# Vorlage_ATmega2560-16AU.net
KiCad netlist of a schematic drawn in EAGLE
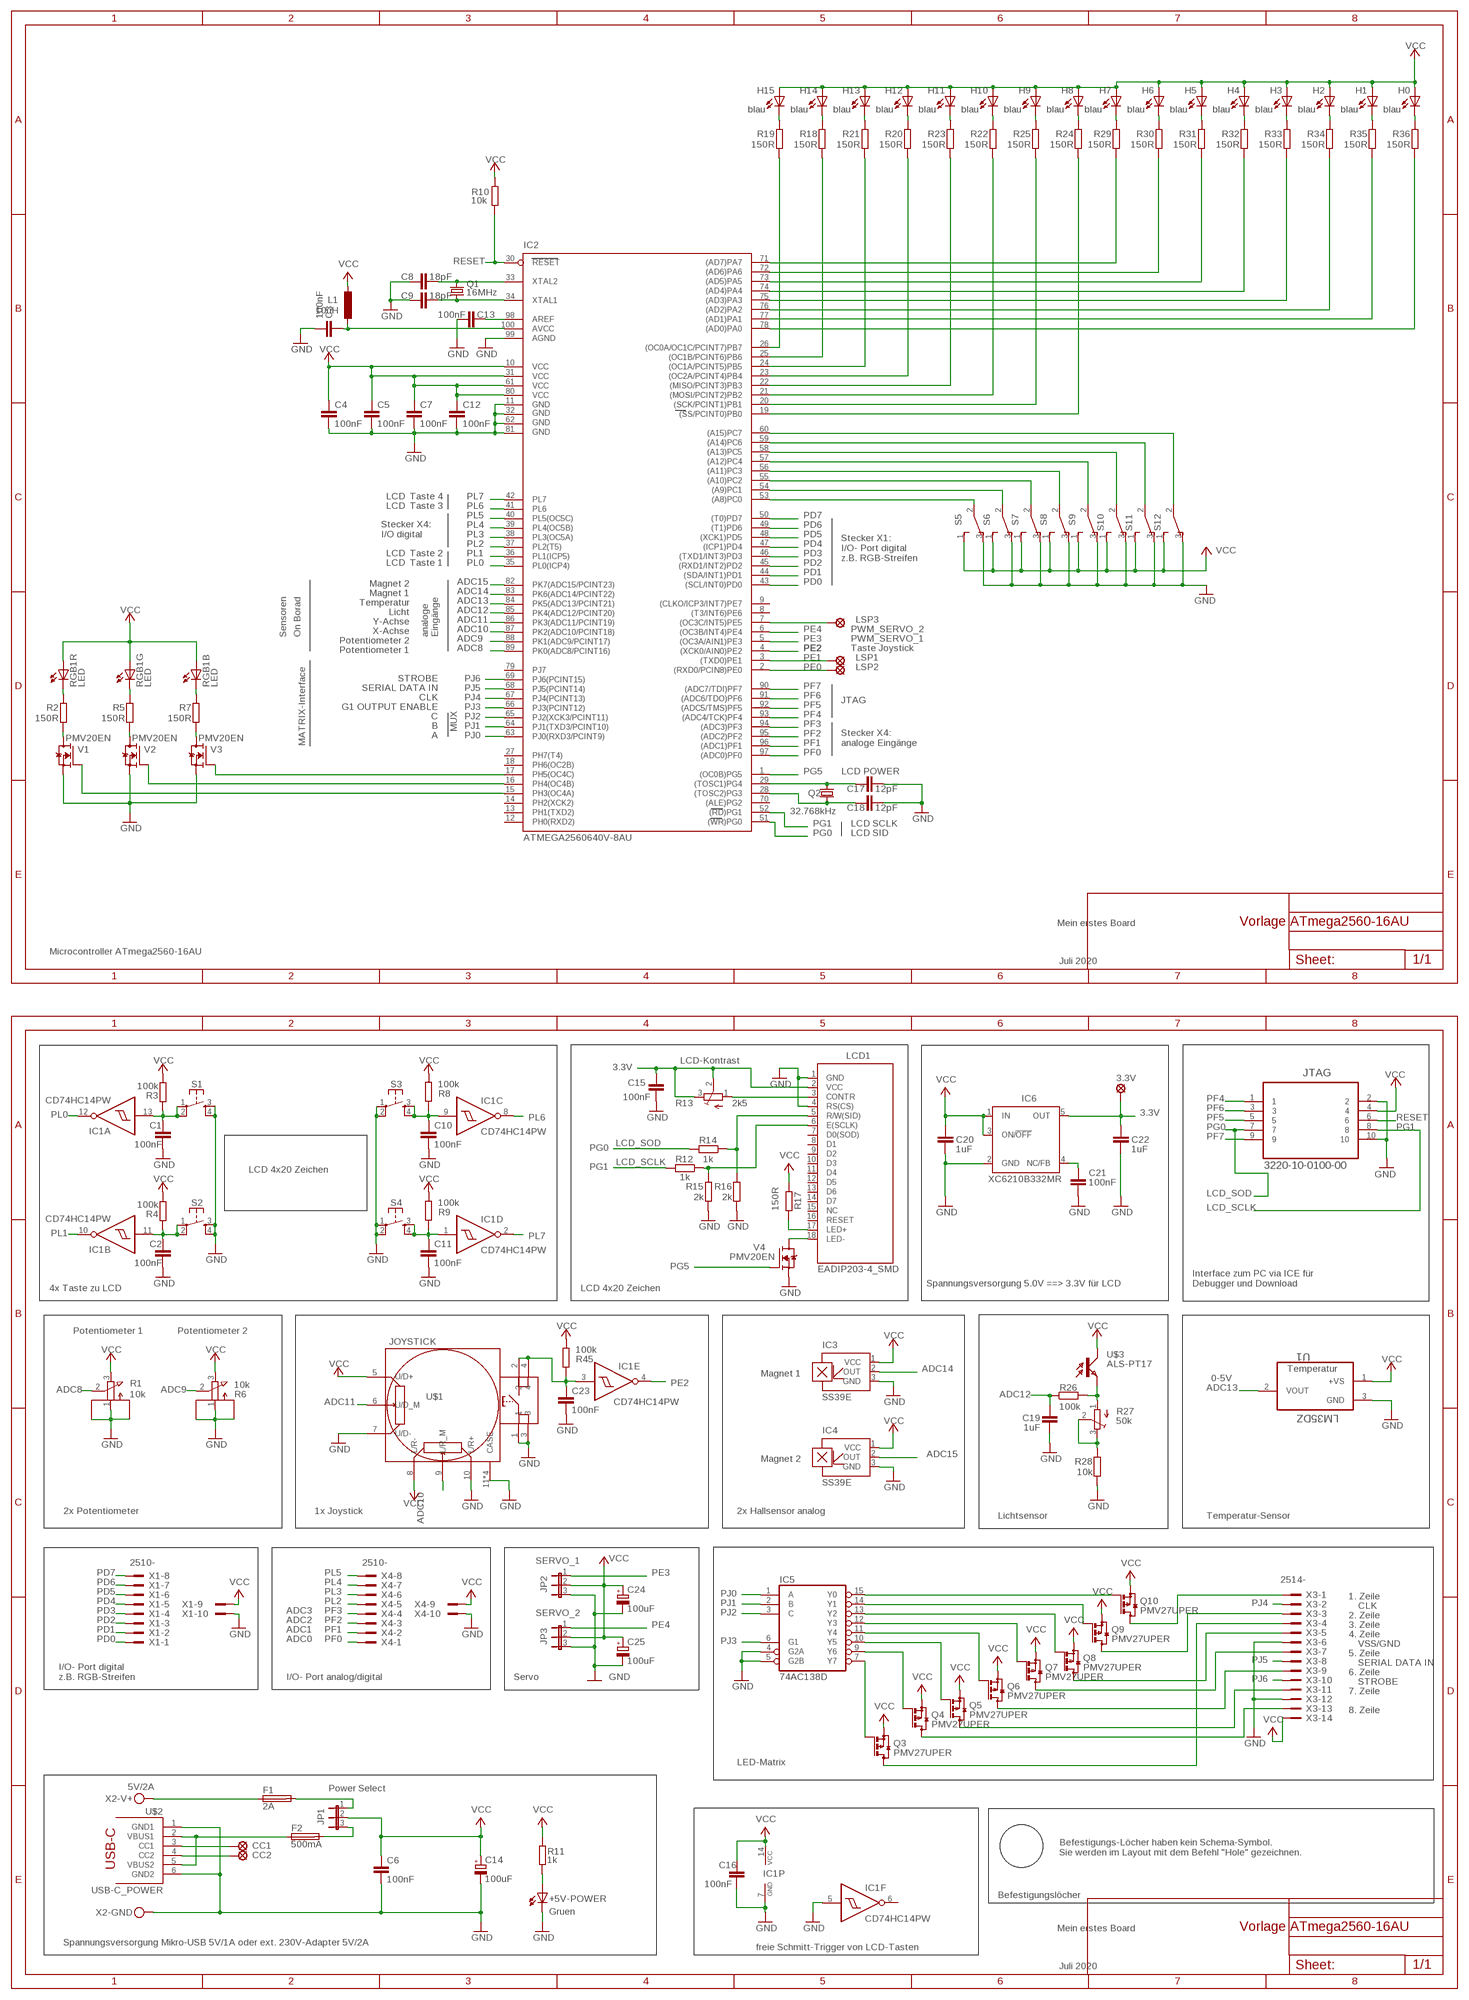
[diagram p0: schematic, sheet 1]

(export (version "E")
  (design (tool "Eeschema 10.0.6"))
  (components
    (comp (ref "+5V-POWER")
      (value "Gruen")
      (footprint "eagle-import:CHIPLED_1206")
      (libsource (lib "eagle-import") (part "LEDCHIPLED_1206"))
    )
    (comp (ref "3.3V")
      (value "3.3V")
      (footprint "eagle-import:LSP11")
      (libsource (lib "eagle-import") (part "LSP11"))
    )
    (comp (ref "C1")
      (value "100nF")
      (footprint "eagle-import:C1206")
      (libsource (lib "eagle-import") (part "C-EUC1206"))
    )
    (comp (ref "C2")
      (value "100nF")
      (footprint "eagle-import:C1206")
      (libsource (lib "eagle-import") (part "C-EUC1206"))
    )
    (comp (ref "C3")
      (value "100nF")
      (footprint "eagle-import:C1206")
      (libsource (lib "eagle-import") (part "C-EUC1206"))
    )
    (comp (ref "C4")
      (value "100nF")
      (footprint "eagle-import:C1206")
      (libsource (lib "eagle-import") (part "C-EUC1206"))
    )
    (comp (ref "C5")
      (value "100nF")
      (footprint "eagle-import:C1206")
      (libsource (lib "eagle-import") (part "C-EUC1206"))
    )
    (comp (ref "C6")
      (value "100nF")
      (footprint "eagle-import:C1206")
      (libsource (lib "eagle-import") (part "C-EUC1206"))
    )
    (comp (ref "C7")
      (value "100nF")
      (footprint "eagle-import:C1206")
      (libsource (lib "eagle-import") (part "C-EUC1206"))
    )
    (comp (ref "C8")
      (value "18pF")
      (footprint "eagle-import:C0805K")
      (libsource (lib "eagle-import") (part "C-EUC0805K"))
    )
    (comp (ref "C9")
      (value "18pF")
      (footprint "eagle-import:C0805K")
      (libsource (lib "eagle-import") (part "C-EUC0805K"))
    )
    (comp (ref "C10")
      (value "100nF")
      (footprint "eagle-import:C1206")
      (libsource (lib "eagle-import") (part "C-EUC1206"))
    )
    (comp (ref "C11")
      (value "100nF")
      (footprint "eagle-import:C1206")
      (libsource (lib "eagle-import") (part "C-EUC1206"))
    )
    (comp (ref "C12")
      (value "100nF")
      (footprint "eagle-import:C1206")
      (libsource (lib "eagle-import") (part "C-EUC1206"))
    )
    (comp (ref "C13")
      (value "100nF")
      (footprint "eagle-import:C1206")
      (libsource (lib "eagle-import") (part "C-EUC1206"))
    )
    (comp (ref "C14")
      (value "100uF")
      (footprint "eagle-import:UD-6,3X5,8_NICHICON")
      (libsource (lib "eagle-import") (part "CPOL-EUUD-6,3X8,8"))
    )
    (comp (ref "C15")
      (value "100nF")
      (footprint "eagle-import:C1206")
      (libsource (lib "eagle-import") (part "C-EUC1206"))
    )
    (comp (ref "C16")
      (value "100nF")
      (footprint "eagle-import:C1206")
      (libsource (lib "eagle-import") (part "C-EUC1206"))
    )
    (comp (ref "C17")
      (value "12pF")
      (footprint "eagle-import:C0805K")
      (libsource (lib "eagle-import") (part "C-EUC0805K"))
    )
    (comp (ref "C18")
      (value "12pF")
      (footprint "eagle-import:C0805K")
      (libsource (lib "eagle-import") (part "C-EUC0805K"))
    )
    (comp (ref "C19")
      (value "1uF")
      (footprint "eagle-import:C1206")
      (libsource (lib "eagle-import") (part "C-EUC1206"))
    )
    (comp (ref "C20")
      (value "1uF")
      (footprint "eagle-import:C1206")
      (libsource (lib "eagle-import") (part "C-EUC1206"))
    )
    (comp (ref "C21")
      (value "100nF")
      (footprint "eagle-import:C1206")
      (libsource (lib "eagle-import") (part "C-EUC1206"))
    )
    (comp (ref "C22")
      (value "1uF")
      (footprint "eagle-import:C1206")
      (libsource (lib "eagle-import") (part "C-EUC1206"))
    )
    (comp (ref "C23")
      (value "100nF")
      (footprint "eagle-import:C1206")
      (libsource (lib "eagle-import") (part "C-EUC1206"))
    )
    (comp (ref "C24")
      (value "100uF")
      (footprint "eagle-import:UD-6,3X5,8_NICHICON")
      (libsource (lib "eagle-import") (part "CPOL-EUUD-6,3X8,8"))
    )
    (comp (ref "C25")
      (value "100uF")
      (footprint "eagle-import:UD-6,3X5,8_NICHICON")
      (libsource (lib "eagle-import") (part "CPOL-EUUD-6,3X8,8"))
    )
    (comp (ref "CC1")
      (value "LSP11")
      (footprint "eagle-import:LSP11")
      (libsource (lib "eagle-import") (part "LSP11"))
    )
    (comp (ref "CC2")
      (value "LSP11")
      (footprint "eagle-import:LSP11")
      (libsource (lib "eagle-import") (part "LSP11"))
    )
    (comp (ref "F1")
      (value "2A")
      (footprint "eagle-import:F1206")
      (libsource (lib "eagle-import") (part "195601206"))
    )
    (comp (ref "F2")
      (value "500mA")
      (footprint "eagle-import:F1206")
      (libsource (lib "eagle-import") (part "195601206"))
    )
    (comp (ref "H0")
      (value "blau")
      (footprint "eagle-import:CHIPLED_1206")
      (libsource (lib "eagle-import") (part "LEDCHIPLED_1206"))
    )
    (comp (ref "H1")
      (value "blau")
      (footprint "eagle-import:CHIPLED_1206")
      (libsource (lib "eagle-import") (part "LEDCHIPLED_1206"))
    )
    (comp (ref "H2")
      (value "blau")
      (footprint "eagle-import:CHIPLED_1206")
      (libsource (lib "eagle-import") (part "LEDCHIPLED_1206"))
    )
    (comp (ref "H3")
      (value "blau")
      (footprint "eagle-import:CHIPLED_1206")
      (libsource (lib "eagle-import") (part "LEDCHIPLED_1206"))
    )
    (comp (ref "H4")
      (value "blau")
      (footprint "eagle-import:CHIPLED_1206")
      (libsource (lib "eagle-import") (part "LEDCHIPLED_1206"))
    )
    (comp (ref "H5")
      (value "blau")
      (footprint "eagle-import:CHIPLED_1206")
      (libsource (lib "eagle-import") (part "LEDCHIPLED_1206"))
    )
    (comp (ref "H6")
      (value "blau")
      (footprint "eagle-import:CHIPLED_1206")
      (libsource (lib "eagle-import") (part "LEDCHIPLED_1206"))
    )
    (comp (ref "H7")
      (value "blau")
      (footprint "eagle-import:CHIPLED_1206")
      (libsource (lib "eagle-import") (part "LEDCHIPLED_1206"))
    )
    (comp (ref "H8")
      (value "blau")
      (footprint "eagle-import:CHIPLED_1206")
      (libsource (lib "eagle-import") (part "LEDCHIPLED_1206"))
    )
    (comp (ref "H9")
      (value "blau")
      (footprint "eagle-import:CHIPLED_1206")
      (libsource (lib "eagle-import") (part "LEDCHIPLED_1206"))
    )
    (comp (ref "H10")
      (value "blau")
      (footprint "eagle-import:CHIPLED_1206")
      (libsource (lib "eagle-import") (part "LEDCHIPLED_1206"))
    )
    (comp (ref "H11")
      (value "blau")
      (footprint "eagle-import:CHIPLED_1206")
      (libsource (lib "eagle-import") (part "LEDCHIPLED_1206"))
    )
    (comp (ref "H12")
      (value "blau")
      (footprint "eagle-import:CHIPLED_1206")
      (libsource (lib "eagle-import") (part "LEDCHIPLED_1206"))
    )
    (comp (ref "H13")
      (value "blau")
      (footprint "eagle-import:CHIPLED_1206")
      (libsource (lib "eagle-import") (part "LEDCHIPLED_1206"))
    )
    (comp (ref "H14")
      (value "blau")
      (footprint "eagle-import:CHIPLED_1206")
      (libsource (lib "eagle-import") (part "LEDCHIPLED_1206"))
    )
    (comp (ref "H15")
      (value "blau")
      (footprint "eagle-import:CHIPLED_1206")
      (libsource (lib "eagle-import") (part "LEDCHIPLED_1206"))
    )
    (comp (ref "IC1")
      (value "CD74HC14PW")
      (footprint "eagle-import:SO14")
      (libsource (lib "eagle-import") (part "7414D"))
    )
    (comp (ref "IC2")
      (value "ATMEGA2560640V-8AU")
      (footprint "eagle-import:TQFP100")
      (libsource (lib "eagle-import") (part "ATMEGA2560AU640V-8"))
    )
    (comp (ref "IC3")
      (value "SS39E")
      (footprint "eagle-import:SOT23-W")
      (fields (field (name "MF") "ALLEGRO MICROSYSTEMS, INC.") (field (name "MPN") "A1301ELHLT-T"))
      (libsource (lib "eagle-import") (part "A13?LH01"))
    )
    (comp (ref "IC4")
      (value "SS39E")
      (footprint "eagle-import:SOT23-W")
      (fields (field (name "MF") "ALLEGRO MICROSYSTEMS, INC.") (field (name "MPN") "A1301ELHLT-T"))
      (libsource (lib "eagle-import") (part "A13?LH01"))
    )
    (comp (ref "IC5")
      (value "74AC138D")
      (footprint "eagle-import:SO16")
      (libsource (lib "eagle-import") (part "74138DAC"))
    )
    (comp (ref "IC6")
      (value "XC6210B332MR")
      (footprint "eagle-import:SOT23-DBV")
      (libsource (lib "eagle-import") (part "LP2985-XXDBVR"))
    )
    (comp (ref "JP1")
      (value "Power Select")
      (footprint "eagle-import:JP2")
      (libsource (lib "eagle-import") (part "JP2E"))
    )
    (comp (ref "JP2")
      (value "SERVO_1")
      (footprint "eagle-import:JP2")
      (libsource (lib "eagle-import") (part "JP2E"))
    )
    (comp (ref "JP3")
      (value "SERVO_2")
      (footprint "eagle-import:JP2")
      (libsource (lib "eagle-import") (part "JP2E"))
    )
    (comp (ref "JTAG")
      (value "3220-10-0100-00")
      (footprint "eagle-import:SAMTEC_FTS-105-01-L-D")
      (fields (field (name "MPN") "FTS-105-01-L-D"))
      (libsource (lib "eagle-import") (part "FTS-105-01-L-D"))
    )
    (comp (ref "L1")
      (value "10uH")
      (footprint "eagle-import:L2825P")
      (libsource (lib "eagle-import") (part "L-EUL2825P"))
    )
    (comp (ref "LCD1")
      (value "EADIP203-4_SMD")
      (footprint "eagle-import:EADIP203-4SMD")
      (libsource (lib "eagle-import") (part "EADIP203-4EADIP203-4SMD"))
    )
    (comp (ref "LSP1")
      (value "LSP11")
      (footprint "eagle-import:LSP11")
      (libsource (lib "eagle-import") (part "LSP11"))
    )
    (comp (ref "LSP2")
      (value "LSP11")
      (footprint "eagle-import:LSP11")
      (libsource (lib "eagle-import") (part "LSP11"))
    )
    (comp (ref "LSP3")
      (value "LSP11")
      (footprint "eagle-import:LSP11")
      (libsource (lib "eagle-import") (part "LSP11"))
    )
    (comp (ref "Q1")
      (value "16MHz")
      (footprint "eagle-import:HC49UP")
      (libsource (lib "eagle-import") (part "CRYSTALHC49UP"))
    )
    (comp (ref "Q2")
      (value "32.768kHz")
      (footprint "eagle-import:TC38H")
      (libsource (lib "eagle-import") (part "CRYSTALTC38H"))
    )
    (comp (ref "Q3")
      (value "PMV27UPER")
      (footprint "eagle-import:SOT23")
      (libsource (lib "eagle-import") (part "BSS84"))
    )
    (comp (ref "Q4")
      (value "PMV27UPER")
      (footprint "eagle-import:SOT23")
      (libsource (lib "eagle-import") (part "BSS84"))
    )
    (comp (ref "Q5")
      (value "PMV27UPER")
      (footprint "eagle-import:SOT23")
      (libsource (lib "eagle-import") (part "BSS84"))
    )
    (comp (ref "Q6")
      (value "PMV27UPER")
      (footprint "eagle-import:SOT23")
      (libsource (lib "eagle-import") (part "BSS84"))
    )
    (comp (ref "Q7")
      (value "PMV27UPER")
      (footprint "eagle-import:SOT23")
      (libsource (lib "eagle-import") (part "BSS84"))
    )
    (comp (ref "Q8")
      (value "PMV27UPER")
      (footprint "eagle-import:SOT23")
      (libsource (lib "eagle-import") (part "BSS84"))
    )
    (comp (ref "Q9")
      (value "PMV27UPER")
      (footprint "eagle-import:SOT23")
      (libsource (lib "eagle-import") (part "BSS84"))
    )
    (comp (ref "Q10")
      (value "PMV27UPER")
      (footprint "eagle-import:SOT23")
      (libsource (lib "eagle-import") (part "BSS84"))
    )
    (comp (ref "R1")
      (value "10k")
      (footprint "eagle-import:EVUF")
      (libsource (lib "eagle-import") (part "EVUA"))
    )
    (comp (ref "R2")
      (value "150R")
      (footprint "eagle-import:R1206")
      (libsource (lib "eagle-import") (part "R-EU_R1206"))
    )
    (comp (ref "R3")
      (value "100k")
      (footprint "eagle-import:R1206")
      (libsource (lib "eagle-import") (part "R-EU_R1206"))
    )
    (comp (ref "R4")
      (value "100k")
      (footprint "eagle-import:R1206")
      (libsource (lib "eagle-import") (part "R-EU_R1206"))
    )
    (comp (ref "R5")
      (value "150R")
      (footprint "eagle-import:R1206")
      (libsource (lib "eagle-import") (part "R-EU_R1206"))
    )
    (comp (ref "R6")
      (value "10k")
      (footprint "eagle-import:EVUF")
      (libsource (lib "eagle-import") (part "EVUA"))
    )
    (comp (ref "R7")
      (value "150R")
      (footprint "eagle-import:R1206")
      (libsource (lib "eagle-import") (part "R-EU_R1206"))
    )
    (comp (ref "R8")
      (value "100k")
      (footprint "eagle-import:R1206")
      (libsource (lib "eagle-import") (part "R-EU_R1206"))
    )
    (comp (ref "R9")
      (value "100k")
      (footprint "eagle-import:R1206")
      (libsource (lib "eagle-import") (part "R-EU_R1206"))
    )
    (comp (ref "R10")
      (value "10k")
      (footprint "eagle-import:R1206")
      (libsource (lib "eagle-import") (part "R-EU_R1206"))
    )
    (comp (ref "R11")
      (value "1k")
      (footprint "eagle-import:R1206")
      (libsource (lib "eagle-import") (part "R-EU_R1206"))
    )
    (comp (ref "R12")
      (value "1k")
      (footprint "eagle-import:R1206")
      (libsource (lib "eagle-import") (part "R-EU_R1206"))
    )
    (comp (ref "R13")
      (value "2k5")
      (footprint "eagle-import:3223G")
      (libsource (lib "eagle-import") (part "TRIM_EU-3223G"))
    )
    (comp (ref "R14")
      (value "1k")
      (footprint "eagle-import:R1206")
      (libsource (lib "eagle-import") (part "R-EU_R1206"))
    )
    (comp (ref "R15")
      (value "2k")
      (footprint "eagle-import:R1206")
      (libsource (lib "eagle-import") (part "R-EU_R1206"))
    )
    (comp (ref "R16")
      (value "2k")
      (footprint "eagle-import:R1206")
      (libsource (lib "eagle-import") (part "R-EU_R1206"))
    )
    (comp (ref "R17")
      (value "150R")
      (footprint "eagle-import:R1206")
      (libsource (lib "eagle-import") (part "R-EU_R1206"))
    )
    (comp (ref "R18")
      (value "150R")
      (footprint "eagle-import:R1206")
      (libsource (lib "eagle-import") (part "R-EU_R1206"))
    )
    (comp (ref "R19")
      (value "150R")
      (footprint "eagle-import:R1206")
      (libsource (lib "eagle-import") (part "R-EU_R1206"))
    )
    (comp (ref "R20")
      (value "150R")
      (footprint "eagle-import:R1206")
      (libsource (lib "eagle-import") (part "R-EU_R1206"))
    )
    (comp (ref "R21")
      (value "150R")
      (footprint "eagle-import:R1206")
      (libsource (lib "eagle-import") (part "R-EU_R1206"))
    )
    (comp (ref "R22")
      (value "150R")
      (footprint "eagle-import:R1206")
      (libsource (lib "eagle-import") (part "R-EU_R1206"))
    )
    (comp (ref "R23")
      (value "150R")
      (footprint "eagle-import:R1206")
      (libsource (lib "eagle-import") (part "R-EU_R1206"))
    )
    (comp (ref "R24")
      (value "150R")
      (footprint "eagle-import:R1206")
      (libsource (lib "eagle-import") (part "R-EU_R1206"))
    )
    (comp (ref "R25")
      (value "150R")
      (footprint "eagle-import:R1206")
      (libsource (lib "eagle-import") (part "R-EU_R1206"))
    )
    (comp (ref "R26")
      (value "100k")
      (footprint "eagle-import:R1206")
      (libsource (lib "eagle-import") (part "R-EU_R1206"))
    )
    (comp (ref "R27")
      (value "50k")
      (footprint "eagle-import:3223G")
      (libsource (lib "eagle-import") (part "TRIM_EU-3223G"))
    )
    (comp (ref "R28")
      (value "10k")
      (footprint "eagle-import:R1206")
      (libsource (lib "eagle-import") (part "R-EU_R1206"))
    )
    (comp (ref "R29")
      (value "150R")
      (footprint "eagle-import:R1206")
      (libsource (lib "eagle-import") (part "R-EU_R1206"))
    )
    (comp (ref "R30")
      (value "150R")
      (footprint "eagle-import:R1206")
      (libsource (lib "eagle-import") (part "R-EU_R1206"))
    )
    (comp (ref "R31")
      (value "150R")
      (footprint "eagle-import:R1206")
      (libsource (lib "eagle-import") (part "R-EU_R1206"))
    )
    (comp (ref "R32")
      (value "150R")
      (footprint "eagle-import:R1206")
      (libsource (lib "eagle-import") (part "R-EU_R1206"))
    )
    (comp (ref "R33")
      (value "150R")
      (footprint "eagle-import:R1206")
      (libsource (lib "eagle-import") (part "R-EU_R1206"))
    )
    (comp (ref "R34")
      (value "150R")
      (footprint "eagle-import:R1206")
      (libsource (lib "eagle-import") (part "R-EU_R1206"))
    )
    (comp (ref "R35")
      (value "150R")
      (footprint "eagle-import:R1206")
      (libsource (lib "eagle-import") (part "R-EU_R1206"))
    )
    (comp (ref "R36")
      (value "150R")
      (footprint "eagle-import:R1206")
      (libsource (lib "eagle-import") (part "R-EU_R1206"))
    )
    (comp (ref "R45")
      (value "100k")
      (footprint "eagle-import:R1206")
      (libsource (lib "eagle-import") (part "R-EU_R1206"))
    )
    (comp (ref "RGB1")
      (value "LED")
      (footprint "eagle-import:LED_MIT_DIFUSOR")
      (libsource (lib "eagle-import") (part "GM5WA94310AMIT_DIFUSOR"))
    )
    (comp (ref "S1")
      (value "TS42_4PAD")
      (footprint "eagle-import:TS42_4PAD")
      (libsource (lib "eagle-import") (part "TS42_4PAD"))
    )
    (comp (ref "S2")
      (value "TS42_4PAD")
      (footprint "eagle-import:TS42_4PAD")
      (libsource (lib "eagle-import") (part "TS42_4PAD"))
    )
    (comp (ref "S3")
      (value "TS42_4PAD")
      (footprint "eagle-import:TS42_4PAD")
      (libsource (lib "eagle-import") (part "TS42_4PAD"))
    )
    (comp (ref "S4")
      (value "TS42_4PAD")
      (footprint "eagle-import:TS42_4PAD")
      (libsource (lib "eagle-import") (part "TS42_4PAD"))
    )
    (comp (ref "S5")
      (value "TL36POSPDT_5MM")
      (footprint "eagle-import:SPDT_5MM")
      (libsource (lib "eagle-import") (part "TL36POSPDT_5MM"))
    )
    (comp (ref "S6")
      (value "TL36POSPDT_5MM")
      (footprint "eagle-import:SPDT_5MM")
      (libsource (lib "eagle-import") (part "TL36POSPDT_5MM"))
    )
    (comp (ref "S7")
      (value "TL36POSPDT_5MM")
      (footprint "eagle-import:SPDT_5MM")
      (libsource (lib "eagle-import") (part "TL36POSPDT_5MM"))
    )
    (comp (ref "S8")
      (value "TL36POSPDT_5MM")
      (footprint "eagle-import:SPDT_5MM")
      (libsource (lib "eagle-import") (part "TL36POSPDT_5MM"))
    )
    (comp (ref "S9")
      (value "TL36POSPDT_5MM")
      (footprint "eagle-import:SPDT_5MM")
      (libsource (lib "eagle-import") (part "TL36POSPDT_5MM"))
    )
    (comp (ref "S10")
      (value "TL36POSPDT_5MM")
      (footprint "eagle-import:SPDT_5MM")
      (libsource (lib "eagle-import") (part "TL36POSPDT_5MM"))
    )
    (comp (ref "S11")
      (value "TL36POSPDT_5MM")
      (footprint "eagle-import:SPDT_5MM")
      (libsource (lib "eagle-import") (part "TL36POSPDT_5MM"))
    )
    (comp (ref "S12")
      (value "TL36POSPDT_5MM")
      (footprint "eagle-import:SPDT_5MM")
      (libsource (lib "eagle-import") (part "TL36POSPDT_5MM"))
    )
    (comp (ref "U$1")
      (value "JOYSTICK")
      (footprint "eagle-import:RKJXV1224005")
      (libsource (lib "eagle-import") (part "JOYSTICK"))
    )
    (comp (ref "U$2")
      (value "USB-C_POWER")
      (footprint "eagle-import:USB-C")
      (libsource (lib "eagle-import") (part "USB-C_POWER"))
    )
    (comp (ref "U$3")
      (value "ALS-PT17")
      (footprint "eagle-import:SOD232-W")
      (libsource (lib "eagle-import") (part "ALS-PT17-51C"))
    )
    (comp (ref "U1")
      (value "LM35DZ")
      (footprint "eagle-import:TO127P254X495-3P")
      (libsource (lib "eagle-import") (part "LM35DZ"))
    )
    (comp (ref "V1")
      (value "PMV20EN")
      (footprint "eagle-import:SOT23")
      (libsource (lib "eagle-import") (part "BSS138"))
    )
    (comp (ref "V2")
      (value "PMV20EN")
      (footprint "eagle-import:SOT23")
      (libsource (lib "eagle-import") (part "BSS138"))
    )
    (comp (ref "V3")
      (value "PMV20EN")
      (footprint "eagle-import:SOT23")
      (libsource (lib "eagle-import") (part "BSS138"))
    )
    (comp (ref "V4")
      (value "PMV20EN")
      (footprint "eagle-import:SOT23")
      (libsource (lib "eagle-import") (part "BSS138"))
    )
    (comp (ref "X1")
      (value "2510-")
      (footprint "eagle-import:PAK100_2500-10")
      (fields (field (name "MF") "3M") (field (name "MPN") "2510-6002UB"))
      (libsource (lib "eagle-import") (part "2510-"))
    )
    (comp (ref "X2")
      (value "+5V")
      (footprint "eagle-import:MKDSN1,5_2-5,08")
      (fields (field (name "MPN") "MKDSN 1,5/2-5.08"))
      (libsource (lib "eagle-import") (part "MKDSN1,5/2-5,08"))
    )
    (comp (ref "X3")
      (value "2514-")
      (footprint "eagle-import:PAK100_2500-14")
      (libsource (lib "eagle-import") (part "2514-"))
    )
    (comp (ref "X4")
      (value "2510-")
      (footprint "eagle-import:PAK100_2500-10")
      (fields (field (name "MF") "3M") (field (name "MPN") "2510-6002UB"))
      (libsource (lib "eagle-import") (part "2510-"))
    )
  )
  (nets
    (net (code "1") (name "/3.3V") (class "Default")
      (node (ref "3.3V") (pin "MP") (pinfunction "MP_MP") (pintype "passive"))
      (node (ref "C15") (pin "1") (pinfunction "1_1") (pintype "passive"))
      (node (ref "C22") (pin "1") (pinfunction "1_1") (pintype "passive"))
      (node (ref "IC6") (pin "5") (pinfunction "OUT_5") (pintype "passive"))
      (node (ref "LCD1") (pin "2") (pinfunction "VCC_2") (pintype "passive"))
      (node (ref "R13") (pin "2") (pinfunction "S_2") (pintype "passive"))
      (node (ref "R13") (pin "3") (pinfunction "E_3") (pintype "passive"))
    )
    (net (code "2") (name "/ADC8") (class "Default")
      (node (ref "IC2") (pin "89") (pinfunction "PK0(ADC8/PCINT16)_89") (pintype "bidirectional"))
      (node (ref "R1") (pin "2") (pinfunction "S_2") (pintype "passive"))
    )
    (net (code "3") (name "/ADC9") (class "Default")
      (node (ref "IC2") (pin "88") (pinfunction "PK1(ADC9/PCINT17)_88") (pintype "bidirectional"))
      (node (ref "R6") (pin "2") (pinfunction "S_2") (pintype "passive"))
    )
    (net (code "4") (name "/ADC10") (class "Default")
      (node (ref "IC2") (pin "87") (pinfunction "PK2(ADC10/PCINT18)_87") (pintype "bidirectional"))
      (node (ref "U$1") (pin "9") (pinfunction "L/R_M_9") (pintype "bidirectional"))
    )
    (net (code "5") (name "/ADC11") (class "Default")
      (node (ref "IC2") (pin "86") (pinfunction "PK3(ADC11/PCINT19)_86") (pintype "bidirectional"))
      (node (ref "U$1") (pin "6") (pinfunction "U/D_M_6") (pintype "bidirectional"))
    )
    (net (code "6") (name "/ADC12") (class "Default")
      (node (ref "C19") (pin "2") (pinfunction "2_2") (pintype "passive"))
      (node (ref "IC2") (pin "85") (pinfunction "PK4(ADC12/PCINT20)_85") (pintype "bidirectional"))
      (node (ref "R26") (pin "1") (pinfunction "1_1") (pintype "passive"))
    )
    (net (code "7") (name "/ADC13") (class "Default")
      (node (ref "IC2") (pin "84") (pinfunction "PK5(ADC13/PCINT21)_84") (pintype "bidirectional"))
      (node (ref "U1") (pin "2") (pinfunction "VOUT_2") (pintype "output"))
    )
    (net (code "8") (name "/ADC14") (class "Default")
      (node (ref "IC2") (pin "83") (pinfunction "PK6(ADC14/PCINT22)_83") (pintype "bidirectional"))
      (node (ref "IC3") (pin "2") (pinfunction "OUT_2") (pintype "output"))
    )
    (net (code "9") (name "/ADC15") (class "Default")
      (node (ref "IC2") (pin "82") (pinfunction "PK7(ADC15/PCINT23)_82") (pintype "bidirectional"))
      (node (ref "IC4") (pin "2") (pinfunction "OUT_2") (pintype "output"))
    )
    (net (code "10") (name "/PD0") (class "Default")
      (node (ref "IC2") (pin "43") (pinfunction "(SCL/INT0)PD0_43") (pintype "bidirectional"))
      (node (ref "X1") (pin "1") (pinfunction "KL_1") (pintype "passive"))
    )
    (net (code "11") (name "/PD1") (class "Default")
      (node (ref "IC2") (pin "44") (pinfunction "(SDA/INT1)PD1_44") (pintype "bidirectional"))
      (node (ref "X1") (pin "2") (pinfunction "KL_2") (pintype "passive"))
    )
    (net (code "12") (name "/PD2") (class "Default")
      (node (ref "IC2") (pin "45") (pinfunction "(RXD1/INT2)PD2_45") (pintype "bidirectional"))
      (node (ref "X1") (pin "3") (pinfunction "KL_3") (pintype "passive"))
    )
    (net (code "13") (name "/PD3") (class "Default")
      (node (ref "IC2") (pin "46") (pinfunction "(TXD1/INT3)PD3_46") (pintype "bidirectional"))
      (node (ref "X1") (pin "4") (pinfunction "KL_4") (pintype "passive"))
    )
    (net (code "14") (name "/PD4") (class "Default")
      (node (ref "IC2") (pin "47") (pinfunction "(ICP1)PD4_47") (pintype "bidirectional"))
      (node (ref "X1") (pin "5") (pinfunction "KL_5") (pintype "passive"))
    )
    (net (code "15") (name "/PD5") (class "Default")
      (node (ref "IC2") (pin "48") (pinfunction "(XCK1)PD5_48") (pintype "bidirectional"))
      (node (ref "X1") (pin "6") (pinfunction "KL_6") (pintype "passive"))
    )
    (net (code "16") (name "/PD6") (class "Default")
      (node (ref "IC2") (pin "49") (pinfunction "(T1)PD6_49") (pintype "bidirectional"))
      (node (ref "X1") (pin "7") (pinfunction "KL_7") (pintype "passive"))
    )
    (net (code "17") (name "/PD7") (class "Default")
      (node (ref "IC2") (pin "50") (pinfunction "(T0)PD7_50") (pintype "bidirectional"))
      (node (ref "X1") (pin "8") (pinfunction "KL_8") (pintype "passive"))
    )
    (net (code "18") (name "/PE0") (class "Default")
      (node (ref "IC2") (pin "2") (pinfunction "(RXD0/PCIN8)PE0_2") (pintype "bidirectional"))
      (node (ref "LSP2") (pin "MP") (pinfunction "MP_MP") (pintype "passive"))
    )
    (net (code "19") (name "/PE1") (class "Default")
      (node (ref "IC2") (pin "3") (pinfunction "(TXD0)PE1_3") (pintype "bidirectional"))
      (node (ref "LSP1") (pin "MP") (pinfunction "MP_MP") (pintype "passive"))
    )
    (net (code "20") (name "/PE2") (class "Default")
      (node (ref "IC1") (pin "4") (pinfunction "O_4") (pintype "output"))
      (node (ref "IC2") (pin "4") (pinfunction "(XCK0/AIN0)PE2_4") (pintype "bidirectional"))
    )
    (net (code "21") (name "/PE3") (class "Default")
      (node (ref "IC2") (pin "5") (pinfunction "(OC3A/AIN1)PE3_5") (pintype "bidirectional"))
      (node (ref "JP2") (pin "1") (pinfunction "1_1") (pintype "passive"))
    )
    (net (code "22") (name "/PE4") (class "Default")
      (node (ref "IC2") (pin "6") (pinfunction "(OC3B/INT4)PE4_6") (pintype "bidirectional"))
      (node (ref "JP3") (pin "1") (pinfunction "1_1") (pintype "passive"))
    )
    (net (code "23") (name "/PF0") (class "Default")
      (node (ref "IC2") (pin "97") (pinfunction "(ADC0)PF0_97") (pintype "bidirectional"))
      (node (ref "X4") (pin "1") (pinfunction "KL_1") (pintype "passive"))
    )
    (net (code "24") (name "/PF1") (class "Default")
      (node (ref "IC2") (pin "96") (pinfunction "(ADC1)PF1_96") (pintype "bidirectional"))
      (node (ref "X4") (pin "2") (pinfunction "KL_2") (pintype "passive"))
    )
    (net (code "25") (name "/PF2") (class "Default")
      (node (ref "IC2") (pin "95") (pinfunction "(ADC2)PF2_95") (pintype "bidirectional"))
      (node (ref "X4") (pin "3") (pinfunction "KL_3") (pintype "passive"))
    )
    (net (code "26") (name "/PF3") (class "Default")
      (node (ref "IC2") (pin "94") (pinfunction "(ADC3)PF3_94") (pintype "bidirectional"))
      (node (ref "X4") (pin "4") (pinfunction "KL_4") (pintype "passive"))
    )
    (net (code "27") (name "/PF4") (class "Default")
      (node (ref "IC2") (pin "93") (pinfunction "(ADC4/TCK)PF4_93") (pintype "bidirectional"))
      (node (ref "JTAG") (pin "1") (pinfunction "1_1") (pintype "passive"))
    )
    (net (code "28") (name "/PF5") (class "Default")
      (node (ref "IC2") (pin "92") (pinfunction "(ADC5/TMS)PF5_92") (pintype "bidirectional"))
      (node (ref "JTAG") (pin "5") (pinfunction "5_5") (pintype "passive"))
    )
    (net (code "29") (name "/PF6") (class "Default")
      (node (ref "IC2") (pin "91") (pinfunction "(ADC6/TDO)PF6_91") (pintype "bidirectional"))
      (node (ref "JTAG") (pin "3") (pinfunction "3_3") (pintype "passive"))
    )
    (net (code "30") (name "/PF7") (class "Default")
      (node (ref "IC2") (pin "90") (pinfunction "(ADC7/TDI)PF7_90") (pintype "bidirectional"))
      (node (ref "JTAG") (pin "9") (pinfunction "9_9") (pintype "passive"))
    )
    (net (code "31") (name "/PG0") (class "Default")
      (node (ref "IC2") (pin "51") (pinfunction "(WR)PG0_51") (pintype "bidirectional"))
      (node (ref "JTAG") (pin "7") (pinfunction "7_7") (pintype "passive"))
      (node (ref "R14") (pin "2") (pinfunction "2_2") (pintype "passive"))
    )
    (net (code "32") (name "/PG1") (class "Default")
      (node (ref "IC2") (pin "52") (pinfunction "(RD)PG1_52") (pintype "bidirectional"))
      (node (ref "JTAG") (pin "8") (pinfunction "8_8") (pintype "passive"))
      (node (ref "R12") (pin "2") (pinfunction "2_2") (pintype "passive"))
    )
    (net (code "33") (name "/PG5") (class "Default")
      (node (ref "IC2") (pin "1") (pinfunction "(OC0B)PG5_1") (pintype "bidirectional"))
      (node (ref "V4") (pin "1") (pinfunction "G_1") (pintype "passive"))
    )
    (net (code "34") (name "/PJ0") (class "Default")
      (node (ref "IC2") (pin "63") (pinfunction "PJ0(RXD3/PCINT9)_63") (pintype "bidirectional"))
      (node (ref "IC5") (pin "1") (pinfunction "A_1") (pintype "input"))
    )
    (net (code "35") (name "/PJ1") (class "Default")
      (node (ref "IC2") (pin "64") (pinfunction "PJ1(TXD3/PCINT10)_64") (pintype "bidirectional"))
      (node (ref "IC5") (pin "2") (pinfunction "B_2") (pintype "input"))
    )
    (net (code "36") (name "/PJ2") (class "Default")
      (node (ref "IC2") (pin "65") (pinfunction "PJ2(XCK3/PCINT11)_65") (pintype "bidirectional"))
      (node (ref "IC5") (pin "3") (pinfunction "C_3") (pintype "input"))
    )
    (net (code "37") (name "/PJ3") (class "Default")
      (node (ref "IC2") (pin "66") (pinfunction "PJ3(PCINT12)_66") (pintype "bidirectional"))
      (node (ref "IC5") (pin "6") (pinfunction "G1_6") (pintype "input"))
    )
    (net (code "38") (name "/PJ4") (class "Default")
      (node (ref "IC2") (pin "67") (pinfunction "PJ4(PCINT13)_67") (pintype "bidirectional"))
      (node (ref "X3") (pin "2") (pinfunction "KL_2") (pintype "passive"))
    )
    (net (code "39") (name "/PJ5") (class "Default")
      (node (ref "IC2") (pin "68") (pinfunction "PJ5(PCINT14)_68") (pintype "bidirectional"))
      (node (ref "X3") (pin "8") (pinfunction "KL_8") (pintype "passive"))
    )
    (net (code "40") (name "/PJ6") (class "Default")
      (node (ref "IC2") (pin "69") (pinfunction "PJ6(PCINT15)_69") (pintype "bidirectional"))
      (node (ref "X3") (pin "10") (pinfunction "KL_10") (pintype "passive"))
    )
    (net (code "41") (name "/PL0") (class "Default")
      (node (ref "IC1") (pin "12") (pinfunction "O_12") (pintype "output"))
      (node (ref "IC2") (pin "35") (pinfunction "PL0(ICP4)_35") (pintype "bidirectional"))
    )
    (net (code "42") (name "/PL1") (class "Default")
      (node (ref "IC1") (pin "10") (pinfunction "O_10") (pintype "output"))
      (node (ref "IC2") (pin "36") (pinfunction "PL1(ICP5)_36") (pintype "bidirectional"))
    )
    (net (code "43") (name "/PL2") (class "Default")
      (node (ref "IC2") (pin "37") (pinfunction "PL2(T5)_37") (pintype "bidirectional"))
      (node (ref "X4") (pin "5") (pinfunction "KL_5") (pintype "passive"))
    )
    (net (code "44") (name "/PL3") (class "Default")
      (node (ref "IC2") (pin "38") (pinfunction "PL3(OC5A)_38") (pintype "bidirectional"))
      (node (ref "X4") (pin "6") (pinfunction "KL_6") (pintype "passive"))
    )
    (net (code "45") (name "/PL4") (class "Default")
      (node (ref "IC2") (pin "39") (pinfunction "PL4(OC5B)_39") (pintype "bidirectional"))
      (node (ref "X4") (pin "7") (pinfunction "KL_7") (pintype "passive"))
    )
    (net (code "46") (name "/PL5") (class "Default")
      (node (ref "IC2") (pin "40") (pinfunction "PL5(OC5C)_40") (pintype "bidirectional"))
      (node (ref "X4") (pin "8") (pinfunction "KL_8") (pintype "passive"))
    )
    (net (code "47") (name "/PL6") (class "Default")
      (node (ref "IC1") (pin "8") (pinfunction "O_8") (pintype "output"))
      (node (ref "IC2") (pin "41") (pinfunction "PL6_41") (pintype "bidirectional"))
    )
    (net (code "48") (name "/PL7") (class "Default")
      (node (ref "IC1") (pin "2") (pinfunction "O_2") (pintype "output"))
      (node (ref "IC2") (pin "42") (pinfunction "PL7_42") (pintype "bidirectional"))
    )
    (net (code "49") (name "/RESET") (class "Default")
      (node (ref "IC2") (pin "30") (pinfunction "RESET_30") (pintype "input"))
      (node (ref "JTAG") (pin "6") (pinfunction "6_6") (pintype "passive"))
      (node (ref "R10") (pin "1") (pinfunction "1_1") (pintype "passive"))
    )
    (net (code "50") (name "GND") (class "Default")
      (node (ref "+5V-POWER") (pin "C") (pinfunction "C_C") (pintype "passive"))
      (node (ref "C1") (pin "2") (pinfunction "2_2") (pintype "passive"))
      (node (ref "C10") (pin "2") (pinfunction "2_2") (pintype "passive"))
      (node (ref "C11") (pin "2") (pinfunction "2_2") (pintype "passive"))
      (node (ref "C12") (pin "2") (pinfunction "2_2") (pintype "passive"))
      (node (ref "C13") (pin "1") (pinfunction "1_1") (pintype "passive"))
      (node (ref "C14") (pin "-") (pinfunction "-_-") (pintype "passive"))
      (node (ref "C15") (pin "2") (pinfunction "2_2") (pintype "passive"))
      (node (ref "C16") (pin "2") (pinfunction "2_2") (pintype "passive"))
      (node (ref "C17") (pin "2") (pinfunction "2_2") (pintype "passive"))
      (node (ref "C18") (pin "2") (pinfunction "2_2") (pintype "passive"))
      (node (ref "C19") (pin "1") (pinfunction "1_1") (pintype "passive"))
      (node (ref "C2") (pin "2") (pinfunction "2_2") (pintype "passive"))
      (node (ref "C20") (pin "2") (pinfunction "2_2") (pintype "passive"))
      (node (ref "C21") (pin "2") (pinfunction "2_2") (pintype "passive"))
      (node (ref "C22") (pin "2") (pinfunction "2_2") (pintype "passive"))
      (node (ref "C23") (pin "2") (pinfunction "2_2") (pintype "passive"))
      (node (ref "C24") (pin "-") (pinfunction "-_-") (pintype "passive"))
      (node (ref "C25") (pin "-") (pinfunction "-_-") (pintype "passive"))
      (node (ref "C3") (pin "1") (pinfunction "1_1") (pintype "passive"))
      (node (ref "C4") (pin "2") (pinfunction "2_2") (pintype "passive"))
      (node (ref "C5") (pin "2") (pinfunction "2_2") (pintype "passive"))
      (node (ref "C6") (pin "2") (pinfunction "2_2") (pintype "passive"))
      (node (ref "C7") (pin "2") (pinfunction "2_2") (pintype "passive"))
      (node (ref "C8") (pin "1") (pinfunction "1_1") (pintype "passive"))
      (node (ref "C9") (pin "2") (pinfunction "2_2") (pintype "passive"))
      (node (ref "IC1") (pin "5") (pinfunction "I_5") (pintype "input"))
      (node (ref "IC1") (pin "7") (pinfunction "GND_7") (pintype "power_in"))
      (node (ref "IC2") (pin "11") (pinfunction "GND_11") (pintype "power_in"))
      (node (ref "IC2") (pin "32") (pinfunction "GND1_32") (pintype "power_in"))
      (node (ref "IC2") (pin "62") (pinfunction "GND2_62") (pintype "power_in"))
      (node (ref "IC2") (pin "81") (pinfunction "GND3_81") (pintype "power_in"))
      (node (ref "IC2") (pin "99") (pinfunction "AGND_99") (pintype "power_in"))
      (node (ref "IC3") (pin "3") (pinfunction "GND_3") (pintype "power_in"))
      (node (ref "IC4") (pin "3") (pinfunction "GND_3") (pintype "power_in"))
      (node (ref "IC5") (pin "4") (pinfunction "G2A_4") (pintype "input"))
      (node (ref "IC5") (pin "5") (pinfunction "G2B_5") (pintype "input"))
      (node (ref "IC6") (pin "2") (pinfunction "GND_2") (pintype "power_in"))
      (node (ref "JP2") (pin "3") (pinfunction "3_3") (pintype "passive"))
      (node (ref "JP3") (pin "3") (pinfunction "3_3") (pintype "passive"))
      (node (ref "JTAG") (pin "10") (pinfunction "10_10") (pintype "passive"))
      (node (ref "JTAG") (pin "2") (pinfunction "2_2") (pintype "passive"))
      (node (ref "LCD1") (pin "1") (pinfunction "GND_1") (pintype "power_in"))
      (node (ref "LCD1") (pin "4") (pinfunction "RS(CS)_4") (pintype "input"))
      (node (ref "R1") (pin "1") (pinfunction "A_1") (pintype "passive"))
      (node (ref "R1") (pin "M1") (pinfunction "P$1_M1") (pintype "bidirectional"))
      (node (ref "R1") (pin "M2") (pinfunction "P$2_M2") (pintype "bidirectional"))
      (node (ref "R15") (pin "1") (pinfunction "1_1") (pintype "passive"))
      (node (ref "R16") (pin "1") (pinfunction "1_1") (pintype "passive"))
      (node (ref "R28") (pin "1") (pinfunction "1_1") (pintype "passive"))
      (node (ref "R6") (pin "1") (pinfunction "A_1") (pintype "passive"))
      (node (ref "R6") (pin "M1") (pinfunction "P$1_M1") (pintype "bidirectional"))
      (node (ref "R6") (pin "M2") (pinfunction "P$2_M2") (pintype "bidirectional"))
      (node (ref "S1") (pin "3") (pinfunction "3_3") (pintype "passive"))
      (node (ref "S1") (pin "4") (pinfunction "4_4") (pintype "passive"))
      (node (ref "S10") (pin "3") (pinfunction "O_3") (pintype "passive"))
      (node (ref "S11") (pin "3") (pinfunction "O_3") (pintype "passive"))
      (node (ref "S12") (pin "3") (pinfunction "O_3") (pintype "passive"))
      (node (ref "S2") (pin "3") (pinfunction "3_3") (pintype "passive"))
      (node (ref "S2") (pin "4") (pinfunction "4_4") (pintype "passive"))
      (node (ref "S3") (pin "1") (pinfunction "1_1") (pintype "passive"))
      (node (ref "S3") (pin "2") (pinfunction "2_2") (pintype "passive"))
      (node (ref "S4") (pin "1") (pinfunction "1_1") (pintype "passive"))
      (node (ref "S4") (pin "2") (pinfunction "2_2") (pintype "passive"))
      (node (ref "S5") (pin "3") (pinfunction "O_3") (pintype "passive"))
      (node (ref "S6") (pin "3") (pinfunction "O_3") (pintype "passive"))
      (node (ref "S7") (pin "3") (pinfunction "O_3") (pintype "passive"))
      (node (ref "S8") (pin "3") (pinfunction "O_3") (pintype "passive"))
      (node (ref "S9") (pin "3") (pinfunction "O_3") (pintype "passive"))
      (node (ref "U$1") (pin "1") (pinfunction "1_1") (pintype "bidirectional"))
      (node (ref "U$1") (pin "10") (pinfunction "L/R+_10") (pintype "bidirectional"))
      (node (ref "U$1") (pin "11") (pinfunction "CASE_11") (pintype "bidirectional"))
      (node (ref "U$1") (pin "12") (pinfunction "CASE_12") (pintype "bidirectional"))
      (node (ref "U$1") (pin "15") (pinfunction "CASE_15") (pintype "bidirectional"))
      (node (ref "U$1") (pin "16") (pinfunction "CASE_16") (pintype "bidirectional"))
      (node (ref "U$1") (pin "3") (pinfunction "3_3") (pintype "bidirectional"))
      (node (ref "U$1") (pin "7") (pinfunction "U/D-_7") (pintype "bidirectional"))
      (node (ref "U$2") (pin "1") (pinfunction "GND1_1") (pintype "bidirectional"))
      (node (ref "U$2") (pin "6") (pinfunction "GND2_6") (pintype "bidirectional"))
      (node (ref "U1") (pin "3") (pinfunction "GND_3") (pintype "passive"))
      (node (ref "V1") (pin "2") (pinfunction "S_2") (pintype "passive"))
      (node (ref "V2") (pin "2") (pinfunction "S_2") (pintype "passive"))
      (node (ref "V3") (pin "2") (pinfunction "S_2") (pintype "passive"))
      (node (ref "V4") (pin "2") (pinfunction "S_2") (pintype "passive"))
      (node (ref "X1") (pin "10") (pinfunction "KL_10") (pintype "passive"))
      (node (ref "X2") (pin "1.1") (pinfunction "KL_1.1") (pintype "passive"))
      (node (ref "X2") (pin "1.2") (pinfunction "KL_1.2") (pintype "passive"))
      (node (ref "X3") (pin "12") (pinfunction "KL_12") (pintype "passive"))
      (node (ref "X3") (pin "6") (pinfunction "KL_6") (pintype "passive"))
      (node (ref "X4") (pin "10") (pinfunction "KL_10") (pintype "passive"))
    )
    (net (code "51") (name "Net-(+5V-POWER-PadA)") (class "Default")
      (node (ref "+5V-POWER") (pin "A") (pinfunction "A_A") (pintype "passive"))
      (node (ref "R11") (pin "1") (pinfunction "1_1") (pintype "passive"))
    )
    (net (code "52") (name "Net-(F1-Pad1)") (class "Default")
      (node (ref "F1") (pin "1") (pinfunction "1_1") (pintype "passive"))
      (node (ref "X2") (pin "2.1") (pinfunction "KL_2.1") (pintype "passive"))
      (node (ref "X2") (pin "2.2") (pinfunction "KL_2.2") (pintype "passive"))
    )
    (net (code "53") (name "Net-(F1-Pad2)") (class "Default")
      (node (ref "F1") (pin "2") (pinfunction "2_2") (pintype "passive"))
      (node (ref "JP1") (pin "1") (pinfunction "1_1") (pintype "passive"))
    )
    (net (code "54") (name "Net-(F2-Pad2)") (class "Default")
      (node (ref "F2") (pin "2") (pinfunction "2_2") (pintype "passive"))
      (node (ref "JP1") (pin "3") (pinfunction "3_3") (pintype "passive"))
    )
    (net (code "55") (name "Net-(H0-PadC)") (class "Default")
      (node (ref "H0") (pin "C") (pinfunction "C_C") (pintype "passive"))
      (node (ref "R36") (pin "2") (pinfunction "2_2") (pintype "passive"))
    )
    (net (code "56") (name "Net-(H1-PadC)") (class "Default")
      (node (ref "H1") (pin "C") (pinfunction "C_C") (pintype "passive"))
      (node (ref "R35") (pin "2") (pinfunction "2_2") (pintype "passive"))
    )
    (net (code "57") (name "Net-(H2-PadC)") (class "Default")
      (node (ref "H2") (pin "C") (pinfunction "C_C") (pintype "passive"))
      (node (ref "R34") (pin "2") (pinfunction "2_2") (pintype "passive"))
    )
    (net (code "58") (name "Net-(H3-PadC)") (class "Default")
      (node (ref "H3") (pin "C") (pinfunction "C_C") (pintype "passive"))
      (node (ref "R33") (pin "2") (pinfunction "2_2") (pintype "passive"))
    )
    (net (code "59") (name "Net-(H4-PadC)") (class "Default")
      (node (ref "H4") (pin "C") (pinfunction "C_C") (pintype "passive"))
      (node (ref "R32") (pin "2") (pinfunction "2_2") (pintype "passive"))
    )
    (net (code "60") (name "Net-(H5-PadC)") (class "Default")
      (node (ref "H5") (pin "C") (pinfunction "C_C") (pintype "passive"))
      (node (ref "R31") (pin "2") (pinfunction "2_2") (pintype "passive"))
    )
    (net (code "61") (name "Net-(H6-PadC)") (class "Default")
      (node (ref "H6") (pin "C") (pinfunction "C_C") (pintype "passive"))
      (node (ref "R30") (pin "2") (pinfunction "2_2") (pintype "passive"))
    )
    (net (code "62") (name "Net-(H7-PadC)") (class "Default")
      (node (ref "H7") (pin "C") (pinfunction "C_C") (pintype "passive"))
      (node (ref "R29") (pin "2") (pinfunction "2_2") (pintype "passive"))
    )
    (net (code "63") (name "Net-(H8-PadC)") (class "Default")
      (node (ref "H8") (pin "C") (pinfunction "C_C") (pintype "passive"))
      (node (ref "R24") (pin "2") (pinfunction "2_2") (pintype "passive"))
    )
    (net (code "64") (name "Net-(H9-PadC)") (class "Default")
      (node (ref "H9") (pin "C") (pinfunction "C_C") (pintype "passive"))
      (node (ref "R25") (pin "2") (pinfunction "2_2") (pintype "passive"))
    )
    (net (code "65") (name "Net-(H10-PadC)") (class "Default")
      (node (ref "H10") (pin "C") (pinfunction "C_C") (pintype "passive"))
      (node (ref "R22") (pin "2") (pinfunction "2_2") (pintype "passive"))
    )
    (net (code "66") (name "Net-(H11-PadC)") (class "Default")
      (node (ref "H11") (pin "C") (pinfunction "C_C") (pintype "passive"))
      (node (ref "R23") (pin "2") (pinfunction "2_2") (pintype "passive"))
    )
    (net (code "67") (name "Net-(H12-PadC)") (class "Default")
      (node (ref "H12") (pin "C") (pinfunction "C_C") (pintype "passive"))
      (node (ref "R20") (pin "2") (pinfunction "2_2") (pintype "passive"))
    )
    (net (code "68") (name "Net-(H13-PadC)") (class "Default")
      (node (ref "H13") (pin "C") (pinfunction "C_C") (pintype "passive"))
      (node (ref "R21") (pin "2") (pinfunction "2_2") (pintype "passive"))
    )
    (net (code "69") (name "Net-(H14-PadC)") (class "Default")
      (node (ref "H14") (pin "C") (pinfunction "C_C") (pintype "passive"))
      (node (ref "R18") (pin "2") (pinfunction "2_2") (pintype "passive"))
    )
    (net (code "70") (name "Net-(H15-PadC)") (class "Default")
      (node (ref "H15") (pin "C") (pinfunction "C_C") (pintype "passive"))
      (node (ref "R19") (pin "2") (pinfunction "2_2") (pintype "passive"))
    )
    (net (code "71") (name "Net-(IC1A-I)") (class "Default")
      (node (ref "C1") (pin "1") (pinfunction "1_1") (pintype "passive"))
      (node (ref "IC1") (pin "13") (pinfunction "I_13") (pintype "input"))
      (node (ref "R3") (pin "2") (pinfunction "2_2") (pintype "passive"))
      (node (ref "S1") (pin "1") (pinfunction "1_1") (pintype "passive"))
      (node (ref "S1") (pin "2") (pinfunction "2_2") (pintype "passive"))
    )
    (net (code "72") (name "Net-(IC1B-I)") (class "Default")
      (node (ref "C2") (pin "1") (pinfunction "1_1") (pintype "passive"))
      (node (ref "IC1") (pin "11") (pinfunction "I_11") (pintype "input"))
      (node (ref "R4") (pin "2") (pinfunction "2_2") (pintype "passive"))
      (node (ref "S2") (pin "1") (pinfunction "1_1") (pintype "passive"))
      (node (ref "S2") (pin "2") (pinfunction "2_2") (pintype "passive"))
    )
    (net (code "73") (name "Net-(IC1C-I)") (class "Default")
      (node (ref "C10") (pin "1") (pinfunction "1_1") (pintype "passive"))
      (node (ref "IC1") (pin "9") (pinfunction "I_9") (pintype "input"))
      (node (ref "R8") (pin "1") (pinfunction "1_1") (pintype "passive"))
      (node (ref "S3") (pin "3") (pinfunction "3_3") (pintype "passive"))
      (node (ref "S3") (pin "4") (pinfunction "4_4") (pintype "passive"))
    )
    (net (code "74") (name "Net-(IC1D-I)") (class "Default")
      (node (ref "C11") (pin "1") (pinfunction "1_1") (pintype "passive"))
      (node (ref "IC1") (pin "1") (pinfunction "I_1") (pintype "input"))
      (node (ref "R9") (pin "1") (pinfunction "1_1") (pintype "passive"))
      (node (ref "S4") (pin "3") (pinfunction "3_3") (pintype "passive"))
      (node (ref "S4") (pin "4") (pinfunction "4_4") (pintype "passive"))
    )
    (net (code "75") (name "Net-(IC1E-I)") (class "Default")
      (node (ref "C23") (pin "1") (pinfunction "1_1") (pintype "passive"))
      (node (ref "IC1") (pin "3") (pinfunction "I_3") (pintype "input"))
      (node (ref "R45") (pin "1") (pinfunction "1_1") (pintype "passive"))
      (node (ref "U$1") (pin "2") (pinfunction "2_2") (pintype "bidirectional"))
      (node (ref "U$1") (pin "4") (pinfunction "4_4") (pintype "bidirectional"))
    )
    (net (code "76") (name "Net-(IC2-(A8)PC0)") (class "Default")
      (node (ref "IC2") (pin "53") (pinfunction "(A8)PC0_53") (pintype "bidirectional"))
      (node (ref "S5") (pin "2") (pinfunction "P_2") (pintype "passive"))
    )
    (net (code "77") (name "Net-(IC2-(A9)PC1)") (class "Default")
      (node (ref "IC2") (pin "54") (pinfunction "(A9)PC1_54") (pintype "bidirectional"))
      (node (ref "S6") (pin "2") (pinfunction "P_2") (pintype "passive"))
    )
    (net (code "78") (name "Net-(IC2-(A10)PC2)") (class "Default")
      (node (ref "IC2") (pin "55") (pinfunction "(A10)PC2_55") (pintype "bidirectional"))
      (node (ref "S7") (pin "2") (pinfunction "P_2") (pintype "passive"))
    )
    (net (code "79") (name "Net-(IC2-(A11)PC3)") (class "Default")
      (node (ref "IC2") (pin "56") (pinfunction "(A11)PC3_56") (pintype "bidirectional"))
      (node (ref "S8") (pin "2") (pinfunction "P_2") (pintype "passive"))
    )
    (net (code "80") (name "Net-(IC2-(A12)PC4)") (class "Default")
      (node (ref "IC2") (pin "57") (pinfunction "(A12)PC4_57") (pintype "bidirectional"))
      (node (ref "S9") (pin "2") (pinfunction "P_2") (pintype "passive"))
    )
    (net (code "81") (name "Net-(IC2-(A13)PC5)") (class "Default")
      (node (ref "IC2") (pin "58") (pinfunction "(A13)PC5_58") (pintype "bidirectional"))
      (node (ref "S10") (pin "2") (pinfunction "P_2") (pintype "passive"))
    )
    (net (code "82") (name "Net-(IC2-(A14)PC6)") (class "Default")
      (node (ref "IC2") (pin "59") (pinfunction "(A14)PC6_59") (pintype "bidirectional"))
      (node (ref "S11") (pin "2") (pinfunction "P_2") (pintype "passive"))
    )
    (net (code "83") (name "Net-(IC2-(A15)PC7)") (class "Default")
      (node (ref "IC2") (pin "60") (pinfunction "(A15)PC7_60") (pintype "bidirectional"))
      (node (ref "S12") (pin "2") (pinfunction "P_2") (pintype "passive"))
    )
    (net (code "84") (name "Net-(IC2-(AD0)PA0)") (class "Default")
      (node (ref "IC2") (pin "78") (pinfunction "(AD0)PA0_78") (pintype "bidirectional"))
      (node (ref "R36") (pin "1") (pinfunction "1_1") (pintype "passive"))
    )
    (net (code "85") (name "Net-(IC2-(AD1)PA1)") (class "Default")
      (node (ref "IC2") (pin "77") (pinfunction "(AD1)PA1_77") (pintype "bidirectional"))
      (node (ref "R35") (pin "1") (pinfunction "1_1") (pintype "passive"))
    )
    (net (code "86") (name "Net-(IC2-(AD2)PA2)") (class "Default")
      (node (ref "IC2") (pin "76") (pinfunction "(AD2)PA2_76") (pintype "bidirectional"))
      (node (ref "R34") (pin "1") (pinfunction "1_1") (pintype "passive"))
    )
    (net (code "87") (name "Net-(IC2-(AD3)PA3)") (class "Default")
      (node (ref "IC2") (pin "75") (pinfunction "(AD3)PA3_75") (pintype "bidirectional"))
      (node (ref "R33") (pin "1") (pinfunction "1_1") (pintype "passive"))
    )
    (net (code "88") (name "Net-(IC2-(AD4)PA4)") (class "Default")
      (node (ref "IC2") (pin "74") (pinfunction "(AD4)PA4_74") (pintype "bidirectional"))
      (node (ref "R32") (pin "1") (pinfunction "1_1") (pintype "passive"))
    )
    (net (code "89") (name "Net-(IC2-(AD5)PA5)") (class "Default")
      (node (ref "IC2") (pin "73") (pinfunction "(AD5)PA5_73") (pintype "bidirectional"))
      (node (ref "R31") (pin "1") (pinfunction "1_1") (pintype "passive"))
    )
    (net (code "90") (name "Net-(IC2-(AD6)PA6)") (class "Default")
      (node (ref "IC2") (pin "72") (pinfunction "(AD6)PA6_72") (pintype "bidirectional"))
      (node (ref "R30") (pin "1") (pinfunction "1_1") (pintype "passive"))
    )
    (net (code "91") (name "Net-(IC2-(AD7)PA7)") (class "Default")
      (node (ref "IC2") (pin "71") (pinfunction "(AD7)PA7_71") (pintype "bidirectional"))
      (node (ref "R29") (pin "1") (pinfunction "1_1") (pintype "passive"))
    )
    (net (code "92") (name "Net-(IC2-(MISO{slash}PCINT3)PB3)") (class "Default")
      (node (ref "IC2") (pin "22") (pinfunction "(MISO/PCINT3)PB3_22") (pintype "bidirectional"))
      (node (ref "R23") (pin "1") (pinfunction "1_1") (pintype "passive"))
    )
    (net (code "93") (name "Net-(IC2-(MOSI{slash}PCINT2)PB2)") (class "Default")
      (node (ref "IC2") (pin "21") (pinfunction "(MOSI/PCINT2)PB2_21") (pintype "bidirectional"))
      (node (ref "R22") (pin "1") (pinfunction "1_1") (pintype "passive"))
    )
    (net (code "94") (name "Net-(IC2-(OC0A{slash}OC1C{slash}PCINT7)PB7)") (class "Default")
      (node (ref "IC2") (pin "26") (pinfunction "(OC0A/OC1C/PCINT7)PB7_26") (pintype "bidirectional"))
      (node (ref "R19") (pin "1") (pinfunction "1_1") (pintype "passive"))
    )
    (net (code "95") (name "Net-(IC2-(OC1A{slash}PCINT5)PB5)") (class "Default")
      (node (ref "IC2") (pin "24") (pinfunction "(OC1A/PCINT5)PB5_24") (pintype "bidirectional"))
      (node (ref "R21") (pin "1") (pinfunction "1_1") (pintype "passive"))
    )
    (net (code "96") (name "Net-(IC2-(OC1B{slash}PCINT6)PB6)") (class "Default")
      (node (ref "IC2") (pin "25") (pinfunction "(OC1B/PCINT6)PB6_25") (pintype "bidirectional"))
      (node (ref "R18") (pin "1") (pinfunction "1_1") (pintype "passive"))
    )
    (net (code "97") (name "Net-(IC2-(OC2A{slash}PCINT4)PB4)") (class "Default")
      (node (ref "IC2") (pin "23") (pinfunction "(OC2A/PCINT4)PB4_23") (pintype "bidirectional"))
      (node (ref "R20") (pin "1") (pinfunction "1_1") (pintype "passive"))
    )
    (net (code "98") (name "Net-(IC2-(OC3C{slash}INT5)PE5)") (class "Default")
      (node (ref "IC2") (pin "7") (pinfunction "(OC3C/INT5)PE5_7") (pintype "bidirectional"))
      (node (ref "LSP3") (pin "MP") (pinfunction "MP_MP") (pintype "passive"))
    )
    (net (code "99") (name "Net-(IC2-(SCK{slash}PCINT1)PB1)") (class "Default")
      (node (ref "IC2") (pin "20") (pinfunction "(SCK/PCINT1)PB1_20") (pintype "bidirectional"))
      (node (ref "R25") (pin "1") (pinfunction "1_1") (pintype "passive"))
    )
    (net (code "100") (name "Net-(IC2-(SS{slash}PCINT0)PB0)") (class "Default")
      (node (ref "IC2") (pin "19") (pinfunction "(SS/PCINT0)PB0_19") (pintype "bidirectional"))
      (node (ref "R24") (pin "1") (pinfunction "1_1") (pintype "passive"))
    )
    (net (code "101") (name "Net-(IC2-(TOSC1)PG4)") (class "Default")
      (node (ref "C17") (pin "1") (pinfunction "1_1") (pintype "passive"))
      (node (ref "IC2") (pin "29") (pinfunction "(TOSC1)PG4_29") (pintype "bidirectional"))
      (node (ref "Q2") (pin "1") (pinfunction "1_1") (pintype "passive"))
    )
    (net (code "102") (name "Net-(IC2-(TOSC2)PG3)") (class "Default")
      (node (ref "C18") (pin "1") (pinfunction "1_1") (pintype "passive"))
      (node (ref "IC2") (pin "28") (pinfunction "(TOSC2)PG3_28") (pintype "bidirectional"))
      (node (ref "Q2") (pin "2") (pinfunction "2_2") (pintype "passive"))
    )
    (net (code "103") (name "Net-(IC2-AREF)") (class "Default")
      (node (ref "C13") (pin "2") (pinfunction "2_2") (pintype "passive"))
      (node (ref "IC2") (pin "98") (pinfunction "AREF_98") (pintype "bidirectional"))
    )
    (net (code "104") (name "Net-(IC2-AVCC)") (class "Default")
      (node (ref "C3") (pin "2") (pinfunction "2_2") (pintype "passive"))
      (node (ref "IC2") (pin "100") (pinfunction "AVCC_100") (pintype "power_in"))
      (node (ref "L1") (pin "2") (pinfunction "2_2") (pintype "passive"))
    )
    (net (code "105") (name "Net-(IC2-PH3(OC4A))") (class "Default")
      (node (ref "IC2") (pin "15") (pinfunction "PH3(OC4A)_15") (pintype "bidirectional"))
      (node (ref "V1") (pin "1") (pinfunction "G_1") (pintype "passive"))
    )
    (net (code "106") (name "Net-(IC2-PH4(OC4B))") (class "Default")
      (node (ref "IC2") (pin "16") (pinfunction "PH4(OC4B)_16") (pintype "bidirectional"))
      (node (ref "V2") (pin "1") (pinfunction "G_1") (pintype "passive"))
    )
    (net (code "107") (name "Net-(IC2-PH5(OC4C))") (class "Default")
      (node (ref "IC2") (pin "17") (pinfunction "PH5(OC4C)_17") (pintype "bidirectional"))
      (node (ref "V3") (pin "1") (pinfunction "G_1") (pintype "passive"))
    )
    (net (code "108") (name "Net-(IC2-XTAL1)") (class "Default")
      (node (ref "C9") (pin "1") (pinfunction "1_1") (pintype "passive"))
      (node (ref "IC2") (pin "34") (pinfunction "XTAL1_34") (pintype "input"))
      (node (ref "Q1") (pin "1") (pinfunction "1_1") (pintype "passive"))
    )
    (net (code "109") (name "Net-(IC2-XTAL2)") (class "Default")
      (node (ref "C8") (pin "2") (pinfunction "2_2") (pintype "passive"))
      (node (ref "IC2") (pin "33") (pinfunction "XTAL2_33") (pintype "output"))
      (node (ref "Q1") (pin "2") (pinfunction "2_2") (pintype "passive"))
    )
    (net (code "110") (name "Net-(IC5A-Y0)") (class "Default")
      (node (ref "IC5") (pin "15") (pinfunction "Y0_15") (pintype "output"))
      (node (ref "Q10") (pin "1") (pinfunction "G_1") (pintype "passive"))
    )
    (net (code "111") (name "Net-(IC5A-Y1)") (class "Default")
      (node (ref "IC5") (pin "14") (pinfunction "Y1_14") (pintype "output"))
      (node (ref "Q9") (pin "1") (pinfunction "G_1") (pintype "passive"))
    )
    (net (code "112") (name "Net-(IC5A-Y2)") (class "Default")
      (node (ref "IC5") (pin "13") (pinfunction "Y2_13") (pintype "output"))
      (node (ref "Q8") (pin "1") (pinfunction "G_1") (pintype "passive"))
    )
    (net (code "113") (name "Net-(IC5A-Y3)") (class "Default")
      (node (ref "IC5") (pin "12") (pinfunction "Y3_12") (pintype "output"))
      (node (ref "Q7") (pin "1") (pinfunction "G_1") (pintype "passive"))
    )
    (net (code "114") (name "Net-(IC5A-Y4)") (class "Default")
      (node (ref "IC5") (pin "11") (pinfunction "Y4_11") (pintype "output"))
      (node (ref "Q6") (pin "1") (pinfunction "G_1") (pintype "passive"))
    )
    (net (code "115") (name "Net-(IC5A-Y5)") (class "Default")
      (node (ref "IC5") (pin "10") (pinfunction "Y5_10") (pintype "output"))
      (node (ref "Q5") (pin "1") (pinfunction "G_1") (pintype "passive"))
    )
    (net (code "116") (name "Net-(IC5A-Y6)") (class "Default")
      (node (ref "IC5") (pin "9") (pinfunction "Y6_9") (pintype "output"))
      (node (ref "Q4") (pin "1") (pinfunction "G_1") (pintype "passive"))
    )
    (net (code "117") (name "Net-(IC5A-Y7)") (class "Default")
      (node (ref "IC5") (pin "7") (pinfunction "Y7_7") (pintype "output"))
      (node (ref "Q3") (pin "1") (pinfunction "G_1") (pintype "passive"))
    )
    (net (code "118") (name "Net-(IC6-NC{slash}FB)") (class "Default")
      (node (ref "C21") (pin "1") (pinfunction "1_1") (pintype "passive"))
      (node (ref "IC6") (pin "4") (pinfunction "NC/FB_4") (pintype "passive"))
    )
    (net (code "119") (name "Net-(LCD1-CONTR)") (class "Default")
      (node (ref "LCD1") (pin "3") (pinfunction "CONTR_3") (pintype "input"))
      (node (ref "R13") (pin "1") (pinfunction "A_1") (pintype "passive"))
    )
    (net (code "120") (name "Net-(LCD1-E(SCLK))") (class "Default")
      (node (ref "LCD1") (pin "6") (pinfunction "E(SCLK)_6") (pintype "input"))
      (node (ref "R12") (pin "1") (pinfunction "1_1") (pintype "passive"))
      (node (ref "R15") (pin "2") (pinfunction "2_2") (pintype "passive"))
    )
    (net (code "121") (name "Net-(LCD1-LED+)") (class "Default")
      (node (ref "LCD1") (pin "17") (pinfunction "LED+_17") (pintype "passive"))
      (node (ref "R17") (pin "1") (pinfunction "1_1") (pintype "passive"))
    )
    (net (code "122") (name "Net-(LCD1-LED-)") (class "Default")
      (node (ref "LCD1") (pin "18") (pinfunction "LED-_18") (pintype "passive"))
      (node (ref "V4") (pin "3") (pinfunction "D_3") (pintype "passive"))
    )
    (net (code "123") (name "Net-(LCD1-R{slash}W(SID))") (class "Default")
      (node (ref "LCD1") (pin "5") (pinfunction "R/W(SID)_5") (pintype "input"))
      (node (ref "R14") (pin "1") (pinfunction "1_1") (pintype "passive"))
      (node (ref "R16") (pin "2") (pinfunction "2_2") (pintype "passive"))
    )
    (net (code "124") (name "Net-(Q3-D)") (class "Default")
      (node (ref "Q3") (pin "3") (pinfunction "D_3") (pintype "passive"))
      (node (ref "X3") (pin "4") (pinfunction "KL_4") (pintype "passive"))
    )
    (net (code "125") (name "Net-(Q4-D)") (class "Default")
      (node (ref "Q4") (pin "3") (pinfunction "D_3") (pintype "passive"))
      (node (ref "X3") (pin "13") (pinfunction "KL_13") (pintype "passive"))
    )
    (net (code "126") (name "Net-(Q5-D)") (class "Default")
      (node (ref "Q5") (pin "3") (pinfunction "D_3") (pintype "passive"))
      (node (ref "X3") (pin "11") (pinfunction "KL_11") (pintype "passive"))
    )
    (net (code "127") (name "Net-(Q6-D)") (class "Default")
      (node (ref "Q6") (pin "3") (pinfunction "D_3") (pintype "passive"))
      (node (ref "X3") (pin "9") (pinfunction "KL_9") (pintype "passive"))
    )
    (net (code "128") (name "Net-(Q7-D)") (class "Default")
      (node (ref "Q7") (pin "3") (pinfunction "D_3") (pintype "passive"))
      (node (ref "X3") (pin "7") (pinfunction "KL_7") (pintype "passive"))
    )
    (net (code "129") (name "Net-(Q8-D)") (class "Default")
      (node (ref "Q8") (pin "3") (pinfunction "D_3") (pintype "passive"))
      (node (ref "X3") (pin "5") (pinfunction "KL_5") (pintype "passive"))
    )
    (net (code "130") (name "Net-(Q9-D)") (class "Default")
      (node (ref "Q9") (pin "3") (pinfunction "D_3") (pintype "passive"))
      (node (ref "X3") (pin "3") (pinfunction "KL_3") (pintype "passive"))
    )
    (net (code "131") (name "Net-(Q10-D)") (class "Default")
      (node (ref "Q10") (pin "3") (pinfunction "D_3") (pintype "passive"))
      (node (ref "X3") (pin "1") (pinfunction "KL_1") (pintype "passive"))
    )
    (net (code "132") (name "Net-(R27-A)") (class "Default")
      (node (ref "R26") (pin "2") (pinfunction "2_2") (pintype "passive"))
      (node (ref "R27") (pin "1") (pinfunction "A_1") (pintype "passive"))
      (node (ref "U$3") (pin "E") (pinfunction "E_E") (pintype "passive"))
    )
    (net (code "133") (name "Net-(R27-E)") (class "Default")
      (node (ref "R27") (pin "2") (pinfunction "S_2") (pintype "passive"))
      (node (ref "R27") (pin "3") (pinfunction "E_3") (pintype "passive"))
      (node (ref "R28") (pin "2") (pinfunction "2_2") (pintype "passive"))
    )
    (net (code "134") (name "Net-(RGB1A-C)") (class "Default")
      (node (ref "R7") (pin "2") (pinfunction "2_2") (pintype "passive"))
      (node (ref "RGB1") (pin "1") (pinfunction "C_1") (pintype "passive"))
    )
    (net (code "135") (name "Net-(RGB1B-C)") (class "Default")
      (node (ref "R5") (pin "2") (pinfunction "2_2") (pintype "passive"))
      (node (ref "RGB1") (pin "2") (pinfunction "C_2") (pintype "passive"))
    )
    (net (code "136") (name "Net-(RGB1C-C)") (class "Default")
      (node (ref "R2") (pin "2") (pinfunction "2_2") (pintype "passive"))
      (node (ref "RGB1") (pin "3") (pinfunction "C_3") (pintype "passive"))
    )
    (net (code "137") (name "Net-(U$2-CC1)") (class "Default")
      (node (ref "CC1") (pin "MP") (pinfunction "MP_MP") (pintype "passive"))
      (node (ref "U$2") (pin "3") (pinfunction "CC1_3") (pintype "bidirectional"))
    )
    (net (code "138") (name "Net-(U$2-CC2)") (class "Default")
      (node (ref "CC2") (pin "MP") (pinfunction "MP_MP") (pintype "passive"))
      (node (ref "U$2") (pin "4") (pinfunction "CC2_4") (pintype "bidirectional"))
    )
    (net (code "139") (name "Net-(U$2-VBUS1)") (class "Default")
      (node (ref "F2") (pin "1") (pinfunction "1_1") (pintype "passive"))
      (node (ref "U$2") (pin "2") (pinfunction "VBUS1_2") (pintype "bidirectional"))
      (node (ref "U$2") (pin "5") (pinfunction "VBUS2_5") (pintype "bidirectional"))
    )
    (net (code "140") (name "Net-(V1-D)") (class "Default")
      (node (ref "R2") (pin "1") (pinfunction "1_1") (pintype "passive"))
      (node (ref "V1") (pin "3") (pinfunction "D_3") (pintype "passive"))
    )
    (net (code "141") (name "Net-(V2-D)") (class "Default")
      (node (ref "R5") (pin "1") (pinfunction "1_1") (pintype "passive"))
      (node (ref "V2") (pin "3") (pinfunction "D_3") (pintype "passive"))
    )
    (net (code "142") (name "Net-(V3-D)") (class "Default")
      (node (ref "R7") (pin "1") (pinfunction "1_1") (pintype "passive"))
      (node (ref "V3") (pin "3") (pinfunction "D_3") (pintype "passive"))
    )
    (net (code "143") (name "VCC") (class "Default")
      (node (ref "C12") (pin "1") (pinfunction "1_1") (pintype "passive"))
      (node (ref "C14") (pin "+") (pinfunction "+_+") (pintype "passive"))
      (node (ref "C16") (pin "1") (pinfunction "1_1") (pintype "passive"))
      (node (ref "C20") (pin "1") (pinfunction "1_1") (pintype "passive"))
      (node (ref "C24") (pin "+") (pinfunction "+_+") (pintype "passive"))
      (node (ref "C25") (pin "+") (pinfunction "+_+") (pintype "passive"))
      (node (ref "C4") (pin "1") (pinfunction "1_1") (pintype "passive"))
      (node (ref "C5") (pin "1") (pinfunction "1_1") (pintype "passive"))
      (node (ref "C6") (pin "1") (pinfunction "1_1") (pintype "passive"))
      (node (ref "C7") (pin "1") (pinfunction "1_1") (pintype "passive"))
      (node (ref "H0") (pin "A") (pinfunction "A_A") (pintype "passive"))
      (node (ref "H1") (pin "A") (pinfunction "A_A") (pintype "passive"))
      (node (ref "H10") (pin "A") (pinfunction "A_A") (pintype "passive"))
      (node (ref "H11") (pin "A") (pinfunction "A_A") (pintype "passive"))
      (node (ref "H12") (pin "A") (pinfunction "A_A") (pintype "passive"))
      (node (ref "H13") (pin "A") (pinfunction "A_A") (pintype "passive"))
      (node (ref "H14") (pin "A") (pinfunction "A_A") (pintype "passive"))
      (node (ref "H15") (pin "A") (pinfunction "A_A") (pintype "passive"))
      (node (ref "H2") (pin "A") (pinfunction "A_A") (pintype "passive"))
      (node (ref "H3") (pin "A") (pinfunction "A_A") (pintype "passive"))
      (node (ref "H4") (pin "A") (pinfunction "A_A") (pintype "passive"))
      (node (ref "H5") (pin "A") (pinfunction "A_A") (pintype "passive"))
      (node (ref "H6") (pin "A") (pinfunction "A_A") (pintype "passive"))
      (node (ref "H7") (pin "A") (pinfunction "A_A") (pintype "passive"))
      (node (ref "H8") (pin "A") (pinfunction "A_A") (pintype "passive"))
      (node (ref "H9") (pin "A") (pinfunction "A_A") (pintype "passive"))
      (node (ref "IC1") (pin "14") (pinfunction "VCC_14") (pintype "power_in"))
      (node (ref "IC2") (pin "10") (pinfunction "VCC_10") (pintype "power_in"))
      (node (ref "IC2") (pin "31") (pinfunction "VCC1_31") (pintype "power_in"))
      (node (ref "IC2") (pin "61") (pinfunction "VCC2_61") (pintype "power_in"))
      (node (ref "IC2") (pin "80") (pinfunction "VCC3_80") (pintype "power_in"))
      (node (ref "IC3") (pin "1") (pinfunction "VCC_1") (pintype "power_in"))
      (node (ref "IC4") (pin "1") (pinfunction "VCC_1") (pintype "power_in"))
      (node (ref "IC6") (pin "1") (pinfunction "IN_1") (pintype "input"))
      (node (ref "IC6") (pin "3") (pinfunction "ON/~{OFF}_3") (pintype "input"))
      (node (ref "JP1") (pin "2") (pinfunction "2_2") (pintype "passive"))
      (node (ref "JP2") (pin "2") (pinfunction "2_2") (pintype "passive"))
      (node (ref "JP3") (pin "2") (pinfunction "2_2") (pintype "passive"))
      (node (ref "JTAG") (pin "4") (pinfunction "4_4") (pintype "passive"))
      (node (ref "L1") (pin "1") (pinfunction "1_1") (pintype "passive"))
      (node (ref "Q10") (pin "2") (pinfunction "S_2") (pintype "passive"))
      (node (ref "Q3") (pin "2") (pinfunction "S_2") (pintype "passive"))
      (node (ref "Q4") (pin "2") (pinfunction "S_2") (pintype "passive"))
      (node (ref "Q5") (pin "2") (pinfunction "S_2") (pintype "passive"))
      (node (ref "Q6") (pin "2") (pinfunction "S_2") (pintype "passive"))
      (node (ref "Q7") (pin "2") (pinfunction "S_2") (pintype "passive"))
      (node (ref "Q8") (pin "2") (pinfunction "S_2") (pintype "passive"))
      (node (ref "Q9") (pin "2") (pinfunction "S_2") (pintype "passive"))
      (node (ref "R1") (pin "3") (pinfunction "E_3") (pintype "passive"))
      (node (ref "R10") (pin "2") (pinfunction "2_2") (pintype "passive"))
      (node (ref "R11") (pin "2") (pinfunction "2_2") (pintype "passive"))
      (node (ref "R17") (pin "2") (pinfunction "2_2") (pintype "passive"))
      (node (ref "R3") (pin "1") (pinfunction "1_1") (pintype "passive"))
      (node (ref "R4") (pin "1") (pinfunction "1_1") (pintype "passive"))
      (node (ref "R45") (pin "2") (pinfunction "2_2") (pintype "passive"))
      (node (ref "R6") (pin "3") (pinfunction "E_3") (pintype "passive"))
      (node (ref "R8") (pin "2") (pinfunction "2_2") (pintype "passive"))
      (node (ref "R9") (pin "2") (pinfunction "2_2") (pintype "passive"))
      (node (ref "RGB1") (pin "4") (pinfunction "A_4") (pintype "passive"))
      (node (ref "RGB1") (pin "5") (pinfunction "A_5") (pintype "passive"))
      (node (ref "RGB1") (pin "6") (pinfunction "A_6") (pintype "passive"))
      (node (ref "S10") (pin "1") (pinfunction "S_1") (pintype "passive"))
      (node (ref "S11") (pin "1") (pinfunction "S_1") (pintype "passive"))
      (node (ref "S12") (pin "1") (pinfunction "S_1") (pintype "passive"))
      (node (ref "S5") (pin "1") (pinfunction "S_1") (pintype "passive"))
      (node (ref "S6") (pin "1") (pinfunction "S_1") (pintype "passive"))
      (node (ref "S7") (pin "1") (pinfunction "S_1") (pintype "passive"))
      (node (ref "S8") (pin "1") (pinfunction "S_1") (pintype "passive"))
      (node (ref "S9") (pin "1") (pinfunction "S_1") (pintype "passive"))
      (node (ref "U$1") (pin "5") (pinfunction "U/D+_5") (pintype "bidirectional"))
      (node (ref "U$1") (pin "8") (pinfunction "L/R-_8") (pintype "bidirectional"))
      (node (ref "U$3") (pin "C") (pinfunction "C_C") (pintype "passive"))
      (node (ref "U1") (pin "1") (pinfunction "+VS_1") (pintype "passive"))
      (node (ref "X1") (pin "9") (pinfunction "KL_9") (pintype "passive"))
      (node (ref "X3") (pin "14") (pinfunction "KL_14") (pintype "passive"))
      (node (ref "X4") (pin "9") (pinfunction "KL_9") (pintype "passive"))
    )
    (net (code "144") (name "unconnected-(IC1F-O-Pad6)") (class "Default")
      (node (ref "IC1") (pin "6") (pinfunction "O_6") (pintype "output"))
    )
    (net (code "145") (name "unconnected-(IC2-(ALE)PG2-Pad70)") (class "Default")
      (node (ref "IC2") (pin "70") (pinfunction "(ALE)PG2_70") (pintype "bidirectional"))
    )
    (net (code "146") (name "unconnected-(IC2-(CLKO{slash}ICP3{slash}INT7)PE7-Pad9)") (class "Default")
      (node (ref "IC2") (pin "9") (pinfunction "(CLKO/ICP3/INT7)PE7_9") (pintype "bidirectional"))
    )
    (net (code "147") (name "unconnected-(IC2-(T3{slash}INT6)PE6-Pad8)") (class "Default")
      (node (ref "IC2") (pin "8") (pinfunction "(T3/INT6)PE6_8") (pintype "bidirectional"))
    )
    (net (code "148") (name "unconnected-(IC2-PH0(RXD2)-Pad12)") (class "Default")
      (node (ref "IC2") (pin "12") (pinfunction "PH0(RXD2)_12") (pintype "bidirectional"))
    )
    (net (code "149") (name "unconnected-(IC2-PH1(TXD2)-Pad13)") (class "Default")
      (node (ref "IC2") (pin "13") (pinfunction "PH1(TXD2)_13") (pintype "bidirectional"))
    )
    (net (code "150") (name "unconnected-(IC2-PH2(XCK2)-Pad14)") (class "Default")
      (node (ref "IC2") (pin "14") (pinfunction "PH2(XCK2)_14") (pintype "bidirectional"))
    )
    (net (code "151") (name "unconnected-(IC2-PH6(OC2B)-Pad18)") (class "Default")
      (node (ref "IC2") (pin "18") (pinfunction "PH6(OC2B)_18") (pintype "bidirectional"))
    )
    (net (code "152") (name "unconnected-(IC2-PH7(T4)-Pad27)") (class "Default")
      (node (ref "IC2") (pin "27") (pinfunction "PH7(T4)_27") (pintype "bidirectional"))
    )
    (net (code "153") (name "unconnected-(IC2-PJ7-Pad79)") (class "Default")
      (node (ref "IC2") (pin "79") (pinfunction "PJ7_79") (pintype "bidirectional"))
    )
    (net (code "154") (name "unconnected-(LCD1-D0(SOD)-Pad7)") (class "Default")
      (node (ref "LCD1") (pin "7") (pinfunction "D0(SOD)_7") (pintype "no_connect"))
    )
    (net (code "155") (name "unconnected-(LCD1-D1-Pad8)") (class "Default")
      (node (ref "LCD1") (pin "8") (pinfunction "D1_8") (pintype "no_connect"))
    )
    (net (code "156") (name "unconnected-(LCD1-D2-Pad9)") (class "Default")
      (node (ref "LCD1") (pin "9") (pinfunction "D2_9") (pintype "no_connect"))
    )
    (net (code "157") (name "unconnected-(LCD1-D3-Pad10)") (class "Default")
      (node (ref "LCD1") (pin "10") (pinfunction "D3_10") (pintype "no_connect"))
    )
    (net (code "158") (name "unconnected-(LCD1-D4-Pad11)") (class "Default")
      (node (ref "LCD1") (pin "11") (pinfunction "D4_11") (pintype "no_connect"))
    )
    (net (code "159") (name "unconnected-(LCD1-D5-Pad12)") (class "Default")
      (node (ref "LCD1") (pin "12") (pinfunction "D5_12") (pintype "no_connect"))
    )
    (net (code "160") (name "unconnected-(LCD1-D6-Pad13)") (class "Default")
      (node (ref "LCD1") (pin "13") (pinfunction "D6_13") (pintype "no_connect"))
    )
    (net (code "161") (name "unconnected-(LCD1-D7-Pad14)") (class "Default")
      (node (ref "LCD1") (pin "14") (pinfunction "D7_14") (pintype "no_connect"))
    )
    (net (code "162") (name "unconnected-(LCD1-NC-Pad15)") (class "Default")
      (node (ref "LCD1") (pin "15") (pinfunction "NC_15") (pintype "no_connect"))
    )
    (net (code "163") (name "unconnected-(LCD1-RESET-Pad16)") (class "Default")
      (node (ref "LCD1") (pin "16") (pinfunction "RESET_16") (pintype "no_connect"))
    )
  )
)
